# DDR4_260PIN_Connector.net
KiCad netlist of a schematic drawn in Altium Designer
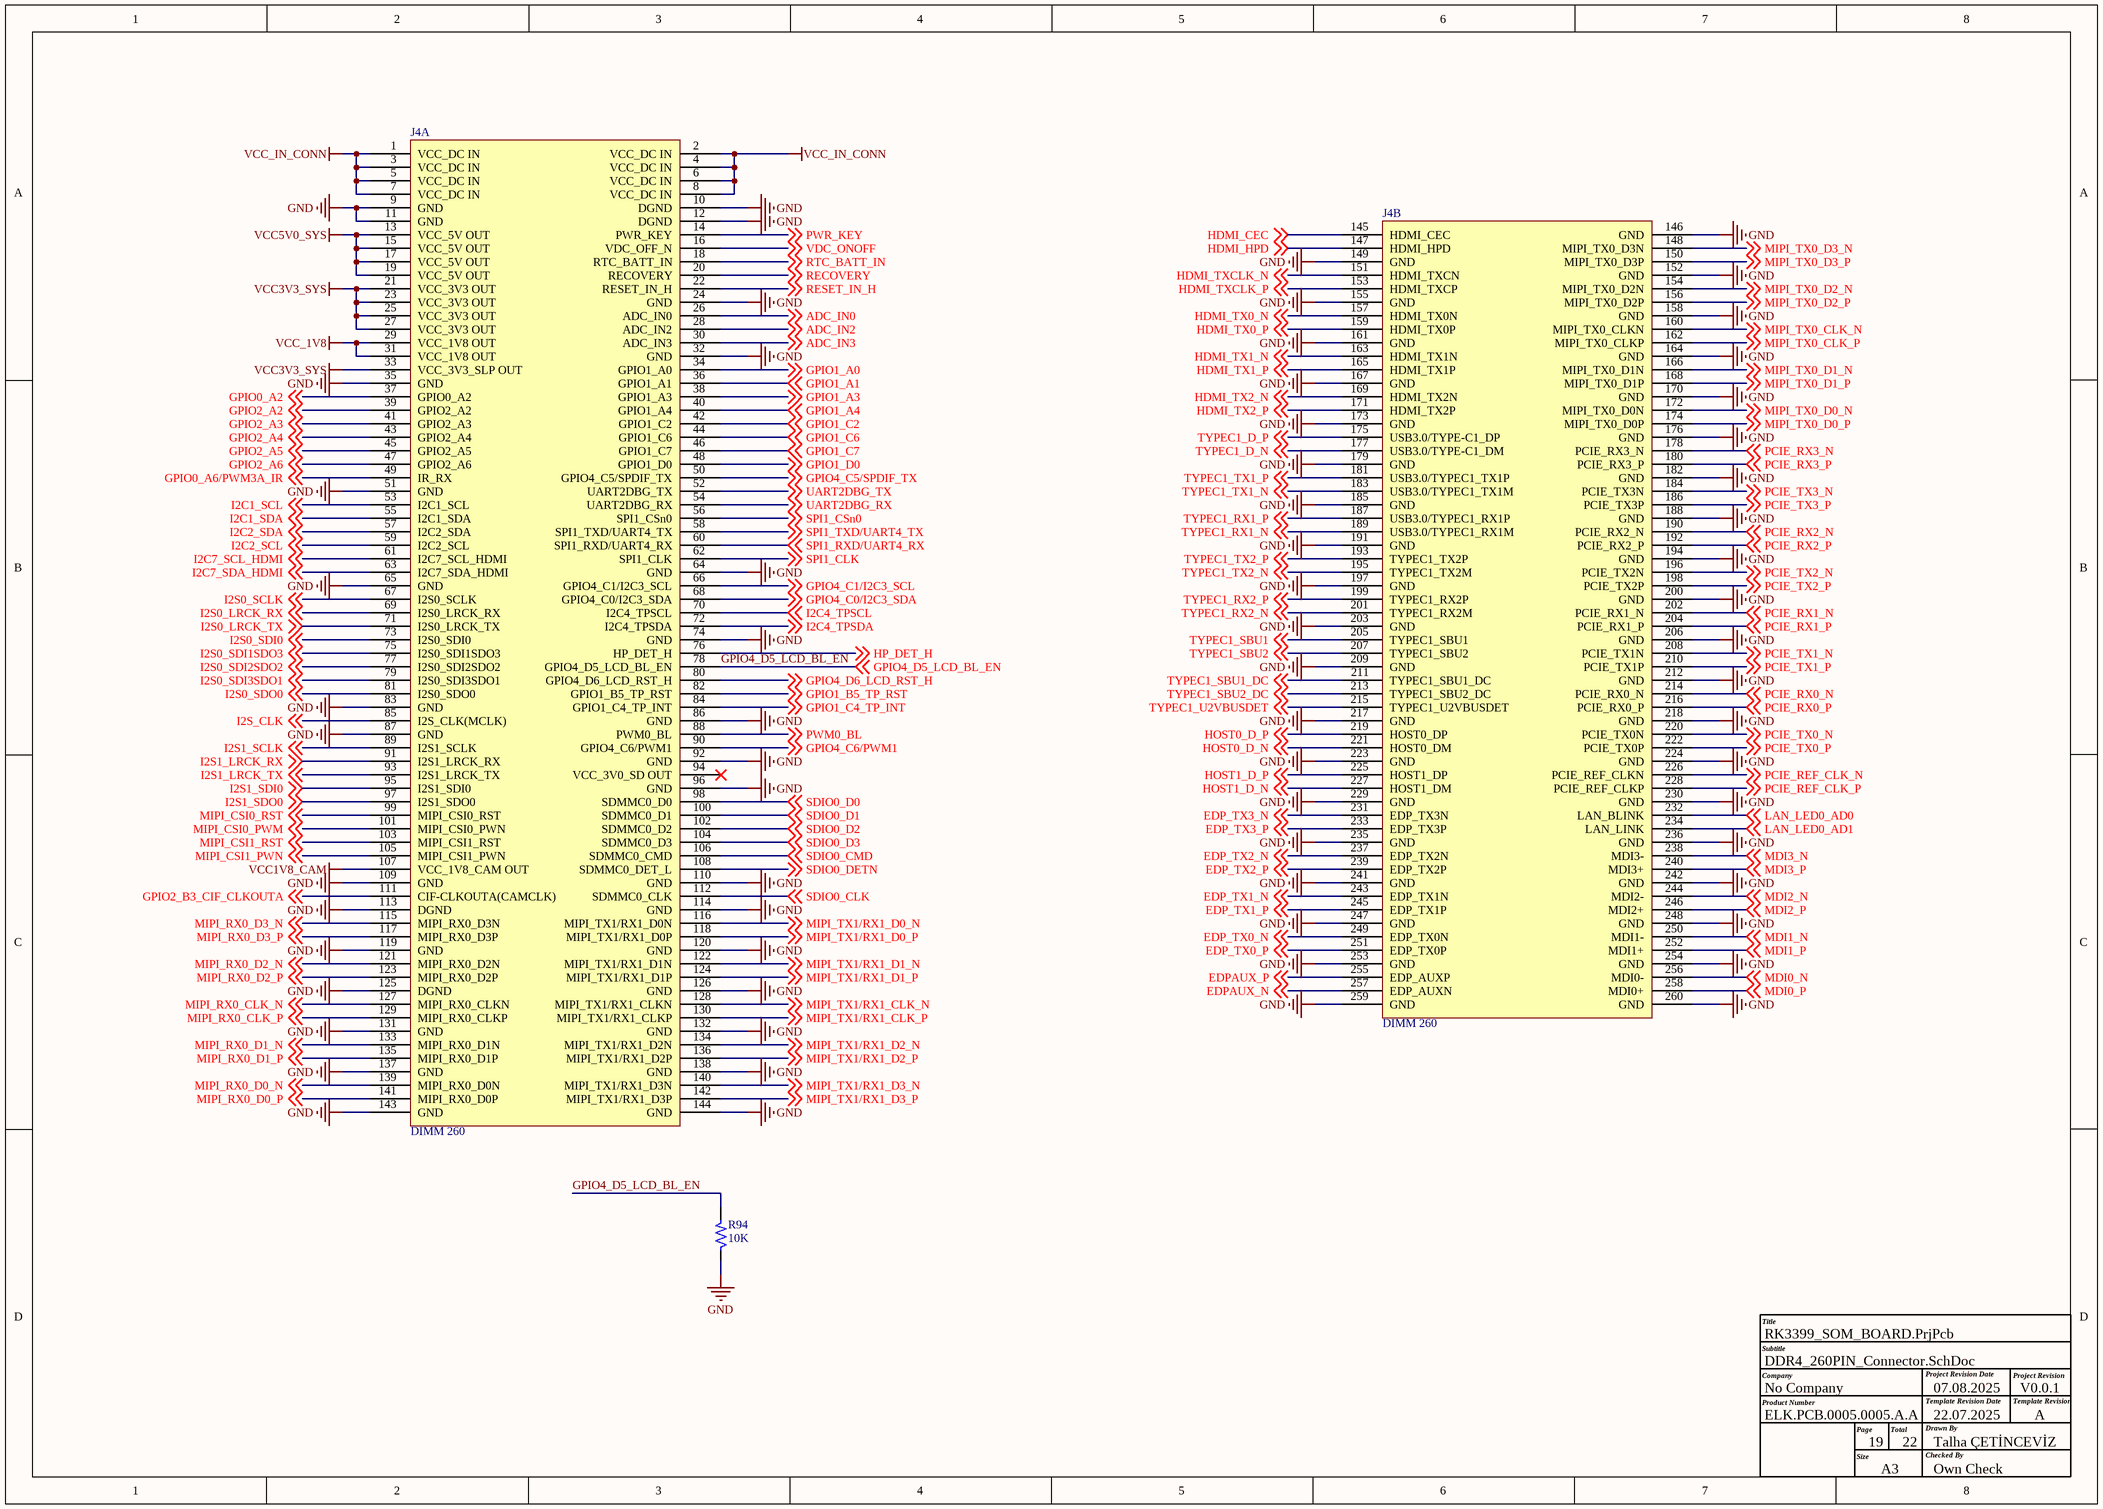
[diagram p0: DDR4_260PIN_Connector.SchDoc]

(export (version "E")
  (design (tool "Eeschema 10.0.6"))
  (components
    (comp (ref "J4")
      (value "DIMM 260")
      (footprint "DIMM260_DDR4")
      (description "Dimm 260 pin smd plating on pcb")
      (fields (field (name "MANUFACTURER") "NA"))
      (libsource (lib "EsteemPCB_SOM_Course_intlib") (part "CON-DIMM_260-SMD"))
    )
    (comp (ref "R94")
      (value "10K")
      (footprint "RES_0402")
      (description "10 kOhms ±1% 0.1W, 1/10W Chip Resistor 0402 (1005 Metric) Anti-Sulfur Thin Film")
      (fields
        (field (name "MANUFACTURER") "Vishay Beyschlag/Draloric/BC Components")
        (field (name "MANUFACTURER PART NUMBER") "MCS04020C1002FE000")
      )
      (libsource (lib "EsteemPCB_SOM_Course_intlib") (part "RES_10K-0.1W-1%-0402"))
    )
  )
  (nets
    (net (code "1") (name "ADC_IN0") (class "Default")
      (node (ref "J4") (pin "26") (pinfunction "ADC_IN0_26") (pintype "passive"))
    )
    (net (code "2") (name "ADC_IN2") (class "Default")
      (node (ref "J4") (pin "28") (pinfunction "ADC_IN2_28") (pintype "passive"))
    )
    (net (code "3") (name "ADC_IN3") (class "Default")
      (node (ref "J4") (pin "30") (pinfunction "ADC_IN3_30") (pintype "passive"))
    )
    (net (code "4") (name "EDPAUX_N") (class "Default")
      (node (ref "J4") (pin "257") (pinfunction "EDP_AUXN_257") (pintype "passive"))
    )
    (net (code "5") (name "EDPAUX_P") (class "Default")
      (node (ref "J4") (pin "255") (pinfunction "EDP_AUXP_255") (pintype "passive"))
    )
    (net (code "6") (name "EDP_TX0_N") (class "Default")
      (node (ref "J4") (pin "249") (pinfunction "EDP_TX0N_249") (pintype "passive"))
    )
    (net (code "7") (name "EDP_TX0_P") (class "Default")
      (node (ref "J4") (pin "251") (pinfunction "EDP_TX0P_251") (pintype "passive"))
    )
    (net (code "8") (name "EDP_TX1_N") (class "Default")
      (node (ref "J4") (pin "243") (pinfunction "EDP_TX1N_243") (pintype "passive"))
    )
    (net (code "9") (name "EDP_TX1_P") (class "Default")
      (node (ref "J4") (pin "245") (pinfunction "EDP_TX1P_245") (pintype "passive"))
    )
    (net (code "10") (name "EDP_TX2_N") (class "Default")
      (node (ref "J4") (pin "237") (pinfunction "EDP_TX2N_237") (pintype "passive"))
    )
    (net (code "11") (name "EDP_TX2_P") (class "Default")
      (node (ref "J4") (pin "239") (pinfunction "EDP_TX2P_239") (pintype "passive"))
    )
    (net (code "12") (name "EDP_TX3_N") (class "Default")
      (node (ref "J4") (pin "231") (pinfunction "EDP_TX3N_231") (pintype "passive"))
    )
    (net (code "13") (name "EDP_TX3_P") (class "Default")
      (node (ref "J4") (pin "233") (pinfunction "EDP_TX3P_233") (pintype "passive"))
    )
    (net (code "14") (name "GND") (class "Default")
      (node (ref "J4") (pin "10") (pinfunction "DGND_10") (pintype "passive"))
      (node (ref "J4") (pin "109") (pinfunction "GND_109") (pintype "passive"))
      (node (ref "J4") (pin "11") (pinfunction "GND_11") (pintype "passive"))
      (node (ref "J4") (pin "110") (pinfunction "GND_110") (pintype "passive"))
      (node (ref "J4") (pin "113") (pinfunction "DGND_113") (pintype "passive"))
      (node (ref "J4") (pin "114") (pinfunction "GND_114") (pintype "passive"))
      (node (ref "J4") (pin "119") (pinfunction "GND_119") (pintype "passive"))
      (node (ref "J4") (pin "12") (pinfunction "DGND_12") (pintype "passive"))
      (node (ref "J4") (pin "120") (pinfunction "GND_120") (pintype "passive"))
      (node (ref "J4") (pin "125") (pinfunction "DGND_125") (pintype "passive"))
      (node (ref "J4") (pin "126") (pinfunction "GND_126") (pintype "passive"))
      (node (ref "J4") (pin "131") (pinfunction "GND_131") (pintype "passive"))
      (node (ref "J4") (pin "132") (pinfunction "GND_132") (pintype "passive"))
      (node (ref "J4") (pin "137") (pinfunction "GND_137") (pintype "passive"))
      (node (ref "J4") (pin "138") (pinfunction "GND_138") (pintype "passive"))
      (node (ref "J4") (pin "143") (pinfunction "GND_143") (pintype "passive"))
      (node (ref "J4") (pin "144") (pinfunction "GND_144") (pintype "passive"))
      (node (ref "J4") (pin "146") (pinfunction "GND_146") (pintype "passive"))
      (node (ref "J4") (pin "149") (pinfunction "GND_149") (pintype "passive"))
      (node (ref "J4") (pin "152") (pinfunction "GND_152") (pintype "passive"))
      (node (ref "J4") (pin "155") (pinfunction "GND_155") (pintype "passive"))
      (node (ref "J4") (pin "158") (pinfunction "GND_158") (pintype "passive"))
      (node (ref "J4") (pin "161") (pinfunction "GND_161") (pintype "passive"))
      (node (ref "J4") (pin "164") (pinfunction "GND_164") (pintype "passive"))
      (node (ref "J4") (pin "167") (pinfunction "GND_167") (pintype "passive"))
      (node (ref "J4") (pin "170") (pinfunction "GND_170") (pintype "passive"))
      (node (ref "J4") (pin "173") (pinfunction "GND_173") (pintype "passive"))
      (node (ref "J4") (pin "176") (pinfunction "GND_176") (pintype "passive"))
      (node (ref "J4") (pin "179") (pinfunction "GND_179") (pintype "passive"))
      (node (ref "J4") (pin "182") (pinfunction "GND_182") (pintype "passive"))
      (node (ref "J4") (pin "185") (pinfunction "GND_185") (pintype "passive"))
      (node (ref "J4") (pin "188") (pinfunction "GND_188") (pintype "passive"))
      (node (ref "J4") (pin "191") (pinfunction "GND_191") (pintype "passive"))
      (node (ref "J4") (pin "194") (pinfunction "GND_194") (pintype "passive"))
      (node (ref "J4") (pin "197") (pinfunction "GND_197") (pintype "passive"))
      (node (ref "J4") (pin "200") (pinfunction "GND_200") (pintype "passive"))
      (node (ref "J4") (pin "203") (pinfunction "GND_203") (pintype "passive"))
      (node (ref "J4") (pin "206") (pinfunction "GND_206") (pintype "passive"))
      (node (ref "J4") (pin "209") (pinfunction "GND_209") (pintype "passive"))
      (node (ref "J4") (pin "212") (pinfunction "GND_212") (pintype "passive"))
      (node (ref "J4") (pin "217") (pinfunction "GND_217") (pintype "passive"))
      (node (ref "J4") (pin "218") (pinfunction "GND_218") (pintype "passive"))
      (node (ref "J4") (pin "223") (pinfunction "GND_223") (pintype "passive"))
      (node (ref "J4") (pin "224") (pinfunction "GND_224") (pintype "passive"))
      (node (ref "J4") (pin "229") (pinfunction "GND_229") (pintype "passive"))
      (node (ref "J4") (pin "230") (pinfunction "GND_230") (pintype "passive"))
      (node (ref "J4") (pin "235") (pinfunction "GND_235") (pintype "passive"))
      (node (ref "J4") (pin "236") (pinfunction "GND_236") (pintype "passive"))
      (node (ref "J4") (pin "24") (pinfunction "GND_24") (pintype "passive"))
      (node (ref "J4") (pin "241") (pinfunction "GND_241") (pintype "passive"))
      (node (ref "J4") (pin "242") (pinfunction "GND_242") (pintype "passive"))
      (node (ref "J4") (pin "247") (pinfunction "GND_247") (pintype "passive"))
      (node (ref "J4") (pin "248") (pinfunction "GND_248") (pintype "passive"))
      (node (ref "J4") (pin "253") (pinfunction "GND_253") (pintype "passive"))
      (node (ref "J4") (pin "254") (pinfunction "GND_254") (pintype "passive"))
      (node (ref "J4") (pin "259") (pinfunction "GND_259") (pintype "passive"))
      (node (ref "J4") (pin "260") (pinfunction "GND_260") (pintype "passive"))
      (node (ref "J4") (pin "32") (pinfunction "GND_32") (pintype "passive"))
      (node (ref "J4") (pin "35") (pinfunction "GND_35") (pintype "passive"))
      (node (ref "J4") (pin "51") (pinfunction "GND_51") (pintype "passive"))
      (node (ref "J4") (pin "64") (pinfunction "GND_64") (pintype "passive"))
      (node (ref "J4") (pin "65") (pinfunction "GND_65") (pintype "passive"))
      (node (ref "J4") (pin "74") (pinfunction "GND_74") (pintype "passive"))
      (node (ref "J4") (pin "83") (pinfunction "GND_83") (pintype "passive"))
      (node (ref "J4") (pin "86") (pinfunction "GND_86") (pintype "passive"))
      (node (ref "J4") (pin "87") (pinfunction "GND_87") (pintype "passive"))
      (node (ref "J4") (pin "9") (pinfunction "GND_9") (pintype "passive"))
      (node (ref "J4") (pin "92") (pinfunction "GND_92") (pintype "passive"))
      (node (ref "J4") (pin "96") (pinfunction "GND_96") (pintype "passive"))
      (node (ref "R94") (pin "1") (pinfunction "1_1") (pintype "passive"))
    )
    (net (code "15") (name "GPIO0_A2") (class "Default")
      (node (ref "J4") (pin "37") (pinfunction "GPIO0_A2_37") (pintype "passive"))
    )
    (net (code "16") (name "GPIO0_A6{slash}PWM3A_IR") (class "Default")
      (node (ref "J4") (pin "49") (pinfunction "IR_RX_49") (pintype "passive"))
    )
    (net (code "17") (name "GPIO1_A0") (class "Default")
      (node (ref "J4") (pin "34") (pinfunction "GPIO1_A0_34") (pintype "passive"))
    )
    (net (code "18") (name "GPIO1_A1") (class "Default")
      (node (ref "J4") (pin "36") (pinfunction "GPIO1_A1_36") (pintype "passive"))
    )
    (net (code "19") (name "GPIO1_A3") (class "Default")
      (node (ref "J4") (pin "38") (pinfunction "GPIO1_A3_38") (pintype "passive"))
    )
    (net (code "20") (name "GPIO1_A4") (class "Default")
      (node (ref "J4") (pin "40") (pinfunction "GPIO1_A4_40") (pintype "passive"))
    )
    (net (code "21") (name "GPIO1_B5_TP_RST") (class "Default")
      (node (ref "J4") (pin "82") (pinfunction "GPIO1_B5_TP_RST_82") (pintype "passive"))
    )
    (net (code "22") (name "GPIO1_C2") (class "Default")
      (node (ref "J4") (pin "42") (pinfunction "GPIO1_C2_42") (pintype "passive"))
    )
    (net (code "23") (name "GPIO1_C4_TP_INT") (class "Default")
      (node (ref "J4") (pin "84") (pinfunction "GPIO1_C4_TP_INT_84") (pintype "passive"))
    )
    (net (code "24") (name "GPIO1_C6") (class "Default")
      (node (ref "J4") (pin "44") (pinfunction "GPIO1_C6_44") (pintype "passive"))
    )
    (net (code "25") (name "GPIO1_C7") (class "Default")
      (node (ref "J4") (pin "46") (pinfunction "GPIO1_C7_46") (pintype "passive"))
    )
    (net (code "26") (name "GPIO1_D0") (class "Default")
      (node (ref "J4") (pin "48") (pinfunction "GPIO1_D0_48") (pintype "passive"))
    )
    (net (code "27") (name "GPIO2_A2") (class "Default")
      (node (ref "J4") (pin "39") (pinfunction "GPIO2_A2_39") (pintype "passive"))
    )
    (net (code "28") (name "GPIO2_A3") (class "Default")
      (node (ref "J4") (pin "41") (pinfunction "GPIO2_A3_41") (pintype "passive"))
    )
    (net (code "29") (name "GPIO2_A4") (class "Default")
      (node (ref "J4") (pin "43") (pinfunction "GPIO2_A4_43") (pintype "passive"))
    )
    (net (code "30") (name "GPIO2_A5") (class "Default")
      (node (ref "J4") (pin "45") (pinfunction "GPIO2_A5_45") (pintype "passive"))
    )
    (net (code "31") (name "GPIO2_A6") (class "Default")
      (node (ref "J4") (pin "47") (pinfunction "GPIO2_A6_47") (pintype "passive"))
    )
    (net (code "32") (name "GPIO2_B3_CIF_CLKOUTA") (class "Default")
      (node (ref "J4") (pin "111") (pinfunction "CIF-CLKOUTA(CAMCLK)_111") (pintype "passive"))
    )
    (net (code "33") (name "GPIO4_C0{slash}I2C3_SDA") (class "Default")
      (node (ref "J4") (pin "68") (pinfunction "GPIO4_C0/I2C3_SDA_68") (pintype "passive"))
    )
    (net (code "34") (name "GPIO4_C1{slash}I2C3_SCL") (class "Default")
      (node (ref "J4") (pin "66") (pinfunction "GPIO4_C1/I2C3_SCL_66") (pintype "passive"))
    )
    (net (code "35") (name "GPIO4_C5{slash}SPDIF_TX") (class "Default")
      (node (ref "J4") (pin "50") (pinfunction "GPIO4_C5/SPDIF_TX_50") (pintype "passive"))
    )
    (net (code "36") (name "GPIO4_C6{slash}PWM1") (class "Default")
      (node (ref "J4") (pin "90") (pinfunction "GPIO4_C6/PWM1_90") (pintype "passive"))
    )
    (net (code "37") (name "GPIO4_D5_LCD_BL_EN") (class "Default")
      (node (ref "J4") (pin "78") (pinfunction "GPIO4_D5_LCD_BL_EN_78") (pintype "passive"))
      (node (ref "R94") (pin "2") (pinfunction "2_2") (pintype "passive"))
    )
    (net (code "38") (name "GPIO4_D6_LCD_RST_H") (class "Default")
      (node (ref "J4") (pin "80") (pinfunction "GPIO4_D6_LCD_RST_H_80") (pintype "passive"))
    )
    (net (code "39") (name "HDMI_CEC") (class "Default")
      (node (ref "J4") (pin "145") (pinfunction "HDMI_CEC_145") (pintype "passive"))
    )
    (net (code "40") (name "HDMI_HPD") (class "Default")
      (node (ref "J4") (pin "147") (pinfunction "HDMI_HPD_147") (pintype "passive"))
    )
    (net (code "41") (name "HDMI_TX0_N") (class "Default")
      (node (ref "J4") (pin "157") (pinfunction "HDMI_TX0N_157") (pintype "passive"))
    )
    (net (code "42") (name "HDMI_TX0_P") (class "Default")
      (node (ref "J4") (pin "159") (pinfunction "HDMI_TX0P_159") (pintype "passive"))
    )
    (net (code "43") (name "HDMI_TX1_N") (class "Default")
      (node (ref "J4") (pin "163") (pinfunction "HDMI_TX1N_163") (pintype "passive"))
    )
    (net (code "44") (name "HDMI_TX1_P") (class "Default")
      (node (ref "J4") (pin "165") (pinfunction "HDMI_TX1P_165") (pintype "passive"))
    )
    (net (code "45") (name "HDMI_TX2_N") (class "Default")
      (node (ref "J4") (pin "169") (pinfunction "HDMI_TX2N_169") (pintype "passive"))
    )
    (net (code "46") (name "HDMI_TX2_P") (class "Default")
      (node (ref "J4") (pin "171") (pinfunction "HDMI_TX2P_171") (pintype "passive"))
    )
    (net (code "47") (name "HDMI_TXCLK_N") (class "Default")
      (node (ref "J4") (pin "151") (pinfunction "HDMI_TXCN_151") (pintype "passive"))
    )
    (net (code "48") (name "HDMI_TXCLK_P") (class "Default")
      (node (ref "J4") (pin "153") (pinfunction "HDMI_TXCP_153") (pintype "passive"))
    )
    (net (code "49") (name "HOST0_D_N") (class "Default")
      (node (ref "J4") (pin "221") (pinfunction "HOST0_DM_221") (pintype "passive"))
    )
    (net (code "50") (name "HOST0_D_P") (class "Default")
      (node (ref "J4") (pin "219") (pinfunction "HOST0_DP_219") (pintype "passive"))
    )
    (net (code "51") (name "HOST1_D_N") (class "Default")
      (node (ref "J4") (pin "227") (pinfunction "HOST1_DM_227") (pintype "passive"))
    )
    (net (code "52") (name "HOST1_D_P") (class "Default")
      (node (ref "J4") (pin "225") (pinfunction "HOST1_DP_225") (pintype "passive"))
    )
    (net (code "53") (name "HP_DET_H") (class "Default")
      (node (ref "J4") (pin "76") (pinfunction "HP_DET_H_76") (pintype "passive"))
    )
    (net (code "54") (name "I2C1_SCL") (class "Default")
      (node (ref "J4") (pin "53") (pinfunction "I2C1_SCL_53") (pintype "passive"))
    )
    (net (code "55") (name "I2C1_SDA") (class "Default")
      (node (ref "J4") (pin "55") (pinfunction "I2C1_SDA_55") (pintype "passive"))
    )
    (net (code "56") (name "I2C2_SCL") (class "Default")
      (node (ref "J4") (pin "59") (pinfunction "I2C2_SCL_59") (pintype "passive"))
    )
    (net (code "57") (name "I2C2_SDA") (class "Default")
      (node (ref "J4") (pin "57") (pinfunction "I2C2_SDA_57") (pintype "passive"))
    )
    (net (code "58") (name "I2C4_TPSCL") (class "Default")
      (node (ref "J4") (pin "70") (pinfunction "I2C4_TPSCL_70") (pintype "passive"))
    )
    (net (code "59") (name "I2C4_TPSDA") (class "Default")
      (node (ref "J4") (pin "72") (pinfunction "I2C4_TPSDA_72") (pintype "passive"))
    )
    (net (code "60") (name "I2C7_SCL_HDMI") (class "Default")
      (node (ref "J4") (pin "61") (pinfunction "I2C7_SCL_HDMI_61") (pintype "passive"))
    )
    (net (code "61") (name "I2C7_SDA_HDMI") (class "Default")
      (node (ref "J4") (pin "63") (pinfunction "I2C7_SDA_HDMI_63") (pintype "passive"))
    )
    (net (code "62") (name "I2S0_LRCK_RX") (class "Default")
      (node (ref "J4") (pin "69") (pinfunction "I2S0_LRCK_RX_69") (pintype "passive"))
    )
    (net (code "63") (name "I2S0_LRCK_TX") (class "Default")
      (node (ref "J4") (pin "71") (pinfunction "I2S0_LRCK_TX_71") (pintype "passive"))
    )
    (net (code "64") (name "I2S0_SCLK") (class "Default")
      (node (ref "J4") (pin "67") (pinfunction "I2S0_SCLK_67") (pintype "passive"))
    )
    (net (code "65") (name "I2S0_SDI0") (class "Default")
      (node (ref "J4") (pin "73") (pinfunction "I2S0_SDI0_73") (pintype "passive"))
    )
    (net (code "66") (name "I2S0_SDI1SDO3") (class "Default")
      (node (ref "J4") (pin "75") (pinfunction "I2S0_SDI1SDO3_75") (pintype "passive"))
    )
    (net (code "67") (name "I2S0_SDI2SDO2") (class "Default")
      (node (ref "J4") (pin "77") (pinfunction "I2S0_SDI2SDO2_77") (pintype "passive"))
    )
    (net (code "68") (name "I2S0_SDI3SDO1") (class "Default")
      (node (ref "J4") (pin "79") (pinfunction "I2S0_SDI3SDO1_79") (pintype "passive"))
    )
    (net (code "69") (name "I2S0_SDO0") (class "Default")
      (node (ref "J4") (pin "81") (pinfunction "I2S0_SDO0_81") (pintype "passive"))
    )
    (net (code "70") (name "I2S1_LRCK_RX") (class "Default")
      (node (ref "J4") (pin "91") (pinfunction "I2S1_LRCK_RX_91") (pintype "passive"))
    )
    (net (code "71") (name "I2S1_LRCK_TX") (class "Default")
      (node (ref "J4") (pin "93") (pinfunction "I2S1_LRCK_TX_93") (pintype "passive"))
    )
    (net (code "72") (name "I2S1_SCLK") (class "Default")
      (node (ref "J4") (pin "89") (pinfunction "I2S1_SCLK_89") (pintype "passive"))
    )
    (net (code "73") (name "I2S1_SDI0") (class "Default")
      (node (ref "J4") (pin "95") (pinfunction "I2S1_SDI0_95") (pintype "passive"))
    )
    (net (code "74") (name "I2S1_SDO0") (class "Default")
      (node (ref "J4") (pin "97") (pinfunction "I2S1_SDO0_97") (pintype "passive"))
    )
    (net (code "75") (name "I2S_CLK") (class "Default")
      (node (ref "J4") (pin "85") (pinfunction "I2S_CLK(MCLK)_85") (pintype "passive"))
    )
    (net (code "76") (name "LAN_LED0_AD0") (class "Default")
      (node (ref "J4") (pin "232") (pinfunction "LAN_BLINK_232") (pintype "passive"))
    )
    (net (code "77") (name "LAN_LED0_AD1") (class "Default")
      (node (ref "J4") (pin "234") (pinfunction "LAN_LINK_234") (pintype "passive"))
    )
    (net (code "78") (name "MDI0_N") (class "Default")
      (node (ref "J4") (pin "256") (pinfunction "MDI0-_256") (pintype "passive"))
    )
    (net (code "79") (name "MDI0_P") (class "Default")
      (node (ref "J4") (pin "258") (pinfunction "MDI0+_258") (pintype "passive"))
    )
    (net (code "80") (name "MDI1_N") (class "Default")
      (node (ref "J4") (pin "250") (pinfunction "MDI1-_250") (pintype "passive"))
    )
    (net (code "81") (name "MDI1_P") (class "Default")
      (node (ref "J4") (pin "252") (pinfunction "MDI1+_252") (pintype "passive"))
    )
    (net (code "82") (name "MDI2_N") (class "Default")
      (node (ref "J4") (pin "244") (pinfunction "MDI2-_244") (pintype "passive"))
    )
    (net (code "83") (name "MDI2_P") (class "Default")
      (node (ref "J4") (pin "246") (pinfunction "MDI2+_246") (pintype "passive"))
    )
    (net (code "84") (name "MDI3_N") (class "Default")
      (node (ref "J4") (pin "238") (pinfunction "MDI3-_238") (pintype "passive"))
    )
    (net (code "85") (name "MDI3_P") (class "Default")
      (node (ref "J4") (pin "240") (pinfunction "MDI3+_240") (pintype "passive"))
    )
    (net (code "86") (name "MIPI_CSI0_PWM") (class "Default")
      (node (ref "J4") (pin "101") (pinfunction "MIPI_CSI0_PWN_101") (pintype "passive"))
    )
    (net (code "87") (name "MIPI_CSI0_RST") (class "Default")
      (node (ref "J4") (pin "99") (pinfunction "MIPI_CSI0_RST_99") (pintype "passive"))
    )
    (net (code "88") (name "MIPI_CSI1_PWN") (class "Default")
      (node (ref "J4") (pin "105") (pinfunction "MIPI_CSI1_PWN_105") (pintype "passive"))
    )
    (net (code "89") (name "MIPI_CSI1_RST") (class "Default")
      (node (ref "J4") (pin "103") (pinfunction "MIPI_CSI1_RST_103") (pintype "passive"))
    )
    (net (code "90") (name "MIPI_RX0_CLK_N") (class "Default")
      (node (ref "J4") (pin "127") (pinfunction "MIPI_RX0_CLKN_127") (pintype "passive"))
    )
    (net (code "91") (name "MIPI_RX0_CLK_P") (class "Default")
      (node (ref "J4") (pin "129") (pinfunction "MIPI_RX0_CLKP_129") (pintype "passive"))
    )
    (net (code "92") (name "MIPI_RX0_D0_N") (class "Default")
      (node (ref "J4") (pin "139") (pinfunction "MIPI_RX0_D0N_139") (pintype "passive"))
    )
    (net (code "93") (name "MIPI_RX0_D0_P") (class "Default")
      (node (ref "J4") (pin "141") (pinfunction "MIPI_RX0_D0P_141") (pintype "passive"))
    )
    (net (code "94") (name "MIPI_RX0_D1_N") (class "Default")
      (node (ref "J4") (pin "133") (pinfunction "MIPI_RX0_D1N_133") (pintype "passive"))
    )
    (net (code "95") (name "MIPI_RX0_D1_P") (class "Default")
      (node (ref "J4") (pin "135") (pinfunction "MIPI_RX0_D1P_135") (pintype "passive"))
    )
    (net (code "96") (name "MIPI_RX0_D2_N") (class "Default")
      (node (ref "J4") (pin "121") (pinfunction "MIPI_RX0_D2N_121") (pintype "passive"))
    )
    (net (code "97") (name "MIPI_RX0_D2_P") (class "Default")
      (node (ref "J4") (pin "123") (pinfunction "MIPI_RX0_D2P_123") (pintype "passive"))
    )
    (net (code "98") (name "MIPI_RX0_D3_N") (class "Default")
      (node (ref "J4") (pin "115") (pinfunction "MIPI_RX0_D3N_115") (pintype "passive"))
    )
    (net (code "99") (name "MIPI_RX0_D3_P") (class "Default")
      (node (ref "J4") (pin "117") (pinfunction "MIPI_RX0_D3P_117") (pintype "passive"))
    )
    (net (code "100") (name "MIPI_TX0_CLK_N") (class "Default")
      (node (ref "J4") (pin "160") (pinfunction "MIPI_TX0_CLKN_160") (pintype "passive"))
    )
    (net (code "101") (name "MIPI_TX0_CLK_P") (class "Default")
      (node (ref "J4") (pin "162") (pinfunction "MIPI_TX0_CLKP_162") (pintype "passive"))
    )
    (net (code "102") (name "MIPI_TX0_D0_N") (class "Default")
      (node (ref "J4") (pin "172") (pinfunction "MIPI_TX0_D0N_172") (pintype "passive"))
    )
    (net (code "103") (name "MIPI_TX0_D0_P") (class "Default")
      (node (ref "J4") (pin "174") (pinfunction "MIPI_TX0_D0P_174") (pintype "passive"))
    )
    (net (code "104") (name "MIPI_TX0_D1_N") (class "Default")
      (node (ref "J4") (pin "166") (pinfunction "MIPI_TX0_D1N_166") (pintype "passive"))
    )
    (net (code "105") (name "MIPI_TX0_D1_P") (class "Default")
      (node (ref "J4") (pin "168") (pinfunction "MIPI_TX0_D1P_168") (pintype "passive"))
    )
    (net (code "106") (name "MIPI_TX0_D2_N") (class "Default")
      (node (ref "J4") (pin "154") (pinfunction "MIPI_TX0_D2N_154") (pintype "passive"))
    )
    (net (code "107") (name "MIPI_TX0_D2_P") (class "Default")
      (node (ref "J4") (pin "156") (pinfunction "MIPI_TX0_D2P_156") (pintype "passive"))
    )
    (net (code "108") (name "MIPI_TX0_D3_N") (class "Default")
      (node (ref "J4") (pin "148") (pinfunction "MIPI_TX0_D3N_148") (pintype "passive"))
    )
    (net (code "109") (name "MIPI_TX0_D3_P") (class "Default")
      (node (ref "J4") (pin "150") (pinfunction "MIPI_TX0_D3P_150") (pintype "passive"))
    )
    (net (code "110") (name "MIPI_TX1{slash}RX1_CLK_N") (class "Default")
      (node (ref "J4") (pin "128") (pinfunction "MIPI_TX1/RX1_CLKN_128") (pintype "passive"))
    )
    (net (code "111") (name "MIPI_TX1{slash}RX1_CLK_P") (class "Default")
      (node (ref "J4") (pin "130") (pinfunction "MIPI_TX1/RX1_CLKP_130") (pintype "passive"))
    )
    (net (code "112") (name "MIPI_TX1{slash}RX1_D0_N") (class "Default")
      (node (ref "J4") (pin "116") (pinfunction "MIPI_TX1/RX1_D0N_116") (pintype "passive"))
    )
    (net (code "113") (name "MIPI_TX1{slash}RX1_D0_P") (class "Default")
      (node (ref "J4") (pin "118") (pinfunction "MIPI_TX1/RX1_D0P_118") (pintype "passive"))
    )
    (net (code "114") (name "MIPI_TX1{slash}RX1_D1_N") (class "Default")
      (node (ref "J4") (pin "122") (pinfunction "MIPI_TX1/RX1_D1N_122") (pintype "passive"))
    )
    (net (code "115") (name "MIPI_TX1{slash}RX1_D1_P") (class "Default")
      (node (ref "J4") (pin "124") (pinfunction "MIPI_TX1/RX1_D1P_124") (pintype "passive"))
    )
    (net (code "116") (name "MIPI_TX1{slash}RX1_D2_N") (class "Default")
      (node (ref "J4") (pin "134") (pinfunction "MIPI_TX1/RX1_D2N_134") (pintype "passive"))
    )
    (net (code "117") (name "MIPI_TX1{slash}RX1_D2_P") (class "Default")
      (node (ref "J4") (pin "136") (pinfunction "MIPI_TX1/RX1_D2P_136") (pintype "passive"))
    )
    (net (code "118") (name "MIPI_TX1{slash}RX1_D3_N") (class "Default")
      (node (ref "J4") (pin "140") (pinfunction "MIPI_TX1/RX1_D3N_140") (pintype "passive"))
    )
    (net (code "119") (name "MIPI_TX1{slash}RX1_D3_P") (class "Default")
      (node (ref "J4") (pin "142") (pinfunction "MIPI_TX1/RX1_D3P_142") (pintype "passive"))
    )
    (net (code "120") (name "PCIE_REF_CLK_N") (class "Default")
      (node (ref "J4") (pin "226") (pinfunction "PCIE_REF_CLKN_226") (pintype "passive"))
    )
    (net (code "121") (name "PCIE_REF_CLK_P") (class "Default")
      (node (ref "J4") (pin "228") (pinfunction "PCIE_REF_CLKP_228") (pintype "passive"))
    )
    (net (code "122") (name "PCIE_RX0_N") (class "Default")
      (node (ref "J4") (pin "214") (pinfunction "PCIE_RX0_N_214") (pintype "passive"))
    )
    (net (code "123") (name "PCIE_RX0_P") (class "Default")
      (node (ref "J4") (pin "216") (pinfunction "PCIE_RX0_P_216") (pintype "passive"))
    )
    (net (code "124") (name "PCIE_RX1_N") (class "Default")
      (node (ref "J4") (pin "202") (pinfunction "PCIE_RX1_N_202") (pintype "passive"))
    )
    (net (code "125") (name "PCIE_RX1_P") (class "Default")
      (node (ref "J4") (pin "204") (pinfunction "PCIE_RX1_P_204") (pintype "passive"))
    )
    (net (code "126") (name "PCIE_RX2_N") (class "Default")
      (node (ref "J4") (pin "190") (pinfunction "PCIE_RX2_N_190") (pintype "passive"))
    )
    (net (code "127") (name "PCIE_RX2_P") (class "Default")
      (node (ref "J4") (pin "192") (pinfunction "PCIE_RX2_P_192") (pintype "passive"))
    )
    (net (code "128") (name "PCIE_RX3_N") (class "Default")
      (node (ref "J4") (pin "178") (pinfunction "PCIE_RX3_N_178") (pintype "passive"))
    )
    (net (code "129") (name "PCIE_RX3_P") (class "Default")
      (node (ref "J4") (pin "180") (pinfunction "PCIE_RX3_P_180") (pintype "passive"))
    )
    (net (code "130") (name "PCIE_TX0_N") (class "Default")
      (node (ref "J4") (pin "220") (pinfunction "PCIE_TX0N_220") (pintype "passive"))
    )
    (net (code "131") (name "PCIE_TX0_P") (class "Default")
      (node (ref "J4") (pin "222") (pinfunction "PCIE_TX0P_222") (pintype "passive"))
    )
    (net (code "132") (name "PCIE_TX1_N") (class "Default")
      (node (ref "J4") (pin "208") (pinfunction "PCIE_TX1N_208") (pintype "passive"))
    )
    (net (code "133") (name "PCIE_TX1_P") (class "Default")
      (node (ref "J4") (pin "210") (pinfunction "PCIE_TX1P_210") (pintype "passive"))
    )
    (net (code "134") (name "PCIE_TX2_N") (class "Default")
      (node (ref "J4") (pin "196") (pinfunction "PCIE_TX2N_196") (pintype "passive"))
    )
    (net (code "135") (name "PCIE_TX2_P") (class "Default")
      (node (ref "J4") (pin "198") (pinfunction "PCIE_TX2P_198") (pintype "passive"))
    )
    (net (code "136") (name "PCIE_TX3_N") (class "Default")
      (node (ref "J4") (pin "184") (pinfunction "PCIE_TX3N_184") (pintype "passive"))
    )
    (net (code "137") (name "PCIE_TX3_P") (class "Default")
      (node (ref "J4") (pin "186") (pinfunction "PCIE_TX3P_186") (pintype "passive"))
    )
    (net (code "138") (name "PWM0_BL") (class "Default")
      (node (ref "J4") (pin "88") (pinfunction "PWM0_BL_88") (pintype "passive"))
    )
    (net (code "139") (name "PWR_KEY") (class "Default")
      (node (ref "J4") (pin "14") (pinfunction "PWR_KEY_14") (pintype "passive"))
    )
    (net (code "140") (name "RECOVERY") (class "Default")
      (node (ref "J4") (pin "20") (pinfunction "RECOVERY_20") (pintype "passive"))
    )
    (net (code "141") (name "RESET_IN_H") (class "Default")
      (node (ref "J4") (pin "22") (pinfunction "RESET_IN_H_22") (pintype "passive"))
    )
    (net (code "142") (name "RTC_BATT_IN") (class "Default")
      (node (ref "J4") (pin "18") (pinfunction "RTC_BATT_IN_18") (pintype "passive"))
    )
    (net (code "143") (name "SDIO0_CLK") (class "Default")
      (node (ref "J4") (pin "112") (pinfunction "SDMMC0_CLK_112") (pintype "passive"))
    )
    (net (code "144") (name "SDIO0_CMD") (class "Default")
      (node (ref "J4") (pin "106") (pinfunction "SDMMC0_CMD_106") (pintype "passive"))
    )
    (net (code "145") (name "SDIO0_D0") (class "Default")
      (node (ref "J4") (pin "98") (pinfunction "SDMMC0_D0_98") (pintype "passive"))
    )
    (net (code "146") (name "SDIO0_D1") (class "Default")
      (node (ref "J4") (pin "100") (pinfunction "SDMMC0_D1_100") (pintype "passive"))
    )
    (net (code "147") (name "SDIO0_D2") (class "Default")
      (node (ref "J4") (pin "102") (pinfunction "SDMMC0_D2_102") (pintype "passive"))
    )
    (net (code "148") (name "SDIO0_D3") (class "Default")
      (node (ref "J4") (pin "104") (pinfunction "SDMMC0_D3_104") (pintype "passive"))
    )
    (net (code "149") (name "SDIO0_DETN") (class "Default")
      (node (ref "J4") (pin "108") (pinfunction "SDMMC0_DET_L_108") (pintype "passive"))
    )
    (net (code "150") (name "SPI1_CLK") (class "Default")
      (node (ref "J4") (pin "62") (pinfunction "SPI1_CLK_62") (pintype "passive"))
    )
    (net (code "151") (name "SPI1_CSn0") (class "Default")
      (node (ref "J4") (pin "56") (pinfunction "SPI1_CSn0_56") (pintype "passive"))
    )
    (net (code "152") (name "SPI1_RXD{slash}UART4_RX") (class "Default")
      (node (ref "J4") (pin "60") (pinfunction "SPI1_RXD/UART4_RX_60") (pintype "passive"))
    )
    (net (code "153") (name "SPI1_TXD{slash}UART4_TX") (class "Default")
      (node (ref "J4") (pin "58") (pinfunction "SPI1_TXD/UART4_TX_58") (pintype "passive"))
    )
    (net (code "154") (name "TYPEC1_D_N") (class "Default")
      (node (ref "J4") (pin "177") (pinfunction "USB3.0/TYPE-C1_DM_177") (pintype "passive"))
    )
    (net (code "155") (name "TYPEC1_D_P") (class "Default")
      (node (ref "J4") (pin "175") (pinfunction "USB3.0/TYPE-C1_DP_175") (pintype "passive"))
    )
    (net (code "156") (name "TYPEC1_RX1_N") (class "Default")
      (node (ref "J4") (pin "189") (pinfunction "USB3.0/TYPEC1_RX1M_189") (pintype "passive"))
    )
    (net (code "157") (name "TYPEC1_RX1_P") (class "Default")
      (node (ref "J4") (pin "187") (pinfunction "USB3.0/TYPEC1_RX1P_187") (pintype "passive"))
    )
    (net (code "158") (name "TYPEC1_RX2_N") (class "Default")
      (node (ref "J4") (pin "201") (pinfunction "TYPEC1_RX2M_201") (pintype "passive"))
    )
    (net (code "159") (name "TYPEC1_RX2_P") (class "Default")
      (node (ref "J4") (pin "199") (pinfunction "TYPEC1_RX2P_199") (pintype "passive"))
    )
    (net (code "160") (name "TYPEC1_SBU1") (class "Default")
      (node (ref "J4") (pin "205") (pinfunction "TYPEC1_SBU1_205") (pintype "passive"))
    )
    (net (code "161") (name "TYPEC1_SBU1_DC") (class "Default")
      (node (ref "J4") (pin "211") (pinfunction "TYPEC1_SBU1_DC_211") (pintype "passive"))
    )
    (net (code "162") (name "TYPEC1_SBU2") (class "Default")
      (node (ref "J4") (pin "207") (pinfunction "TYPEC1_SBU2_207") (pintype "passive"))
    )
    (net (code "163") (name "TYPEC1_SBU2_DC") (class "Default")
      (node (ref "J4") (pin "213") (pinfunction "TYPEC1_SBU2_DC_213") (pintype "passive"))
    )
    (net (code "164") (name "TYPEC1_TX1_N") (class "Default")
      (node (ref "J4") (pin "183") (pinfunction "USB3.0/TYPEC1_TX1M_183") (pintype "passive"))
    )
    (net (code "165") (name "TYPEC1_TX1_P") (class "Default")
      (node (ref "J4") (pin "181") (pinfunction "USB3.0/TYPEC1_TX1P_181") (pintype "passive"))
    )
    (net (code "166") (name "TYPEC1_TX2_N") (class "Default")
      (node (ref "J4") (pin "195") (pinfunction "TYPEC1_TX2M_195") (pintype "passive"))
    )
    (net (code "167") (name "TYPEC1_TX2_P") (class "Default")
      (node (ref "J4") (pin "193") (pinfunction "TYPEC1_TX2P_193") (pintype "passive"))
    )
    (net (code "168") (name "TYPEC1_U2VBUSDET") (class "Default")
      (node (ref "J4") (pin "215") (pinfunction "TYPEC1_U2VBUSDET_215") (pintype "passive"))
    )
    (net (code "169") (name "UART2DBG_RX") (class "Default")
      (node (ref "J4") (pin "54") (pinfunction "UART2DBG_RX_54") (pintype "passive"))
    )
    (net (code "170") (name "UART2DBG_TX") (class "Default")
      (node (ref "J4") (pin "52") (pinfunction "UART2DBG_TX_52") (pintype "passive"))
    )
    (net (code "171") (name "VCC1V8_CAM") (class "Default")
      (node (ref "J4") (pin "107") (pinfunction "VCC_1V8_CAM_OUT_107") (pintype "passive"))
    )
    (net (code "172") (name "VCC3V3_SYS") (class "Default")
      (node (ref "J4") (pin "21") (pinfunction "VCC_3V3_OUT_21") (pintype "passive"))
      (node (ref "J4") (pin "23") (pinfunction "VCC_3V3_OUT_23") (pintype "passive"))
      (node (ref "J4") (pin "25") (pinfunction "VCC_3V3_OUT_25") (pintype "passive"))
      (node (ref "J4") (pin "27") (pinfunction "VCC_3V3_OUT_27") (pintype "passive"))
      (node (ref "J4") (pin "33") (pinfunction "VCC_3V3_SLP_OUT_33") (pintype "passive"))
    )
    (net (code "173") (name "VCC5V0_SYS") (class "Default")
      (node (ref "J4") (pin "13") (pinfunction "VCC_5V_OUT_13") (pintype "passive"))
      (node (ref "J4") (pin "15") (pinfunction "VCC_5V_OUT_15") (pintype "passive"))
      (node (ref "J4") (pin "17") (pinfunction "VCC_5V_OUT_17") (pintype "passive"))
      (node (ref "J4") (pin "19") (pinfunction "VCC_5V_OUT_19") (pintype "passive"))
    )
    (net (code "174") (name "VCC_1V8") (class "Default")
      (node (ref "J4") (pin "29") (pinfunction "VCC_1V8_OUT_29") (pintype "passive"))
      (node (ref "J4") (pin "31") (pinfunction "VCC_1V8_OUT_31") (pintype "passive"))
    )
    (net (code "175") (name "VCC_IN_CONN") (class "Default")
      (node (ref "J4") (pin "1") (pinfunction "VCC_DC_IN_1") (pintype "passive"))
      (node (ref "J4") (pin "2") (pinfunction "VCC_DC_IN_2") (pintype "passive"))
      (node (ref "J4") (pin "3") (pinfunction "VCC_DC_IN_3") (pintype "passive"))
      (node (ref "J4") (pin "4") (pinfunction "VCC_DC_IN_4") (pintype "passive"))
      (node (ref "J4") (pin "5") (pinfunction "VCC_DC_IN_5") (pintype "passive"))
      (node (ref "J4") (pin "6") (pinfunction "VCC_DC_IN_6") (pintype "passive"))
      (node (ref "J4") (pin "7") (pinfunction "VCC_DC_IN_7") (pintype "passive"))
      (node (ref "J4") (pin "8") (pinfunction "VCC_DC_IN_8") (pintype "passive"))
    )
    (net (code "176") (name "VDC_ONOFF") (class "Default")
      (node (ref "J4") (pin "16") (pinfunction "VDC_OFF_N_16") (pintype "passive"))
    )
    (net (code "177") (name "unconnected-(J4A-VCC_3V0_SD_OUT-Pad94)") (class "Default")
      (node (ref "J4") (pin "94") (pinfunction "VCC_3V0_SD_OUT_94") (pintype "passive+no_connect"))
    )
  )
)
